# relay_pro_eagle7x.net
KiCad netlist of a schematic drawn in EAGLE
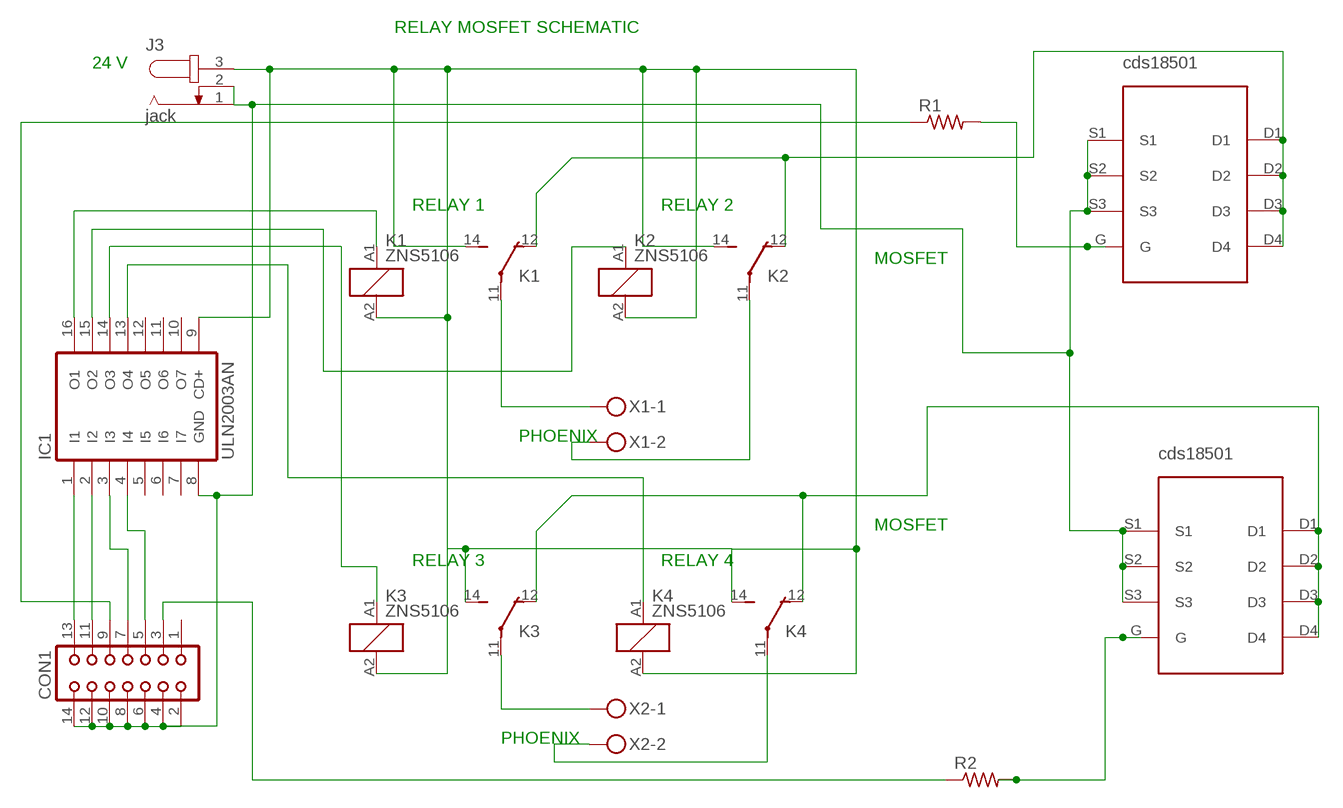
[diagram p0: schematic, sheet 1]

(export (version "E")
  (design (tool "Eeschema 10.0.6"))
  (components
    (comp (ref "CON1")
      (value "CON14")
      (footprint "eagle-import:CON14")
      (libsource (lib "eagle-import") (part "CON14"))
    )
    (comp (ref "IC1")
      (value "ULN2003AN")
      (footprint "eagle-import:DIL16")
      (libsource (lib "eagle-import") (part "ULN2003AN"))
    )
    (comp (ref "J3")
      (value "jack")
      (footprint "eagle-import:SPC4077")
      (libsource (lib "eagle-import") (part "JACK-PLUG0"))
    )
    (comp (ref "K1")
      (value "ZNS5106")
      (footprint "eagle-import:ZN5")
      (libsource (lib "eagle-import") (part "ZNS5106"))
    )
    (comp (ref "K2")
      (value "ZNS5106")
      (footprint "eagle-import:ZN5")
      (libsource (lib "eagle-import") (part "ZNS5106"))
    )
    (comp (ref "K3")
      (value "ZNS5106")
      (footprint "eagle-import:ZN5")
      (libsource (lib "eagle-import") (part "ZNS5106"))
    )
    (comp (ref "K4")
      (value "ZNS5106")
      (footprint "eagle-import:ZN5")
      (libsource (lib "eagle-import") (part "ZNS5106"))
    )
    (comp (ref "R1")
      (value "R-US_R0603")
      (footprint "eagle-import:R0603")
      (libsource (lib "eagle-import") (part "R-US_R0603"))
    )
    (comp (ref "R2")
      (value "R-US_R0603")
      (footprint "eagle-import:R0603")
      (libsource (lib "eagle-import") (part "R-US_R0603"))
    )
    (comp (ref "U$1")
      (value "CSD18503GDS-NEW")
      (footprint "eagle-import:CDS")
      (libsource (lib "eagle-import") (part "CSD18503GDS-NEW"))
    )
    (comp (ref "U$2")
      (value "CSD18503GDS-NEW")
      (footprint "eagle-import:CDS")
      (libsource (lib "eagle-import") (part "CSD18503GDS-NEW"))
    )
    (comp (ref "X1")
      (value "MKDSN1,5/2-5,08")
      (footprint "eagle-import:MKDSN1,5_2-5,08")
      (libsource (lib "eagle-import") (part "MKDSN1,5/2-5,08"))
    )
    (comp (ref "X2")
      (value "MKDSN1,5/2-5,08")
      (footprint "eagle-import:MKDSN1,5_2-5,08")
      (libsource (lib "eagle-import") (part "MKDSN1,5/2-5,08"))
    )
  )
  (nets
    (net (code "1") (name "Net-(CON1-Pad3)") (class "Default")
      (node (ref "CON1") (pin "3") (pinfunction "3_3") (pintype "passive"))
      (node (ref "R2") (pin "1") (pinfunction "1_1") (pintype "passive"))
    )
    (net (code "2") (name "Net-(CON1-Pad9)") (class "Default")
      (node (ref "CON1") (pin "9") (pinfunction "9_9") (pintype "passive"))
      (node (ref "R1") (pin "1") (pinfunction "1_1") (pintype "passive"))
    )
    (net (code "3") (name "Net-(IC1-CD+)") (class "Default")
      (node (ref "IC1") (pin "9") (pinfunction "CD+_9") (pintype "passive"))
      (node (ref "J3") (pin "3") (pinfunction "3_3") (pintype "passive"))
      (node (ref "K1") (pin "14") (pinfunction "S_14") (pintype "passive"))
      (node (ref "K1") (pin "A2") (pinfunction "2_A2") (pintype "passive"))
      (node (ref "K2") (pin "14") (pinfunction "S_14") (pintype "passive"))
      (node (ref "K2") (pin "A2") (pinfunction "2_A2") (pintype "passive"))
      (node (ref "K3") (pin "14") (pinfunction "S_14") (pintype "passive"))
      (node (ref "K3") (pin "A2") (pinfunction "2_A2") (pintype "passive"))
      (node (ref "K4") (pin "14") (pinfunction "S_14") (pintype "passive"))
      (node (ref "K4") (pin "A2") (pinfunction "2_A2") (pintype "passive"))
    )
    (net (code "4") (name "Net-(IC1-GND)") (class "Default")
      (node (ref "CON1") (pin "10") (pinfunction "10_10") (pintype "passive"))
      (node (ref "CON1") (pin "12") (pinfunction "12_12") (pintype "passive"))
      (node (ref "CON1") (pin "14") (pinfunction "14_14") (pintype "passive"))
      (node (ref "CON1") (pin "2") (pinfunction "2_2") (pintype "passive"))
      (node (ref "CON1") (pin "4") (pinfunction "4_4") (pintype "passive"))
      (node (ref "CON1") (pin "6") (pinfunction "6_6") (pintype "passive"))
      (node (ref "CON1") (pin "8") (pinfunction "8_8") (pintype "passive"))
      (node (ref "IC1") (pin "8") (pinfunction "GND_8") (pintype "power_in"))
      (node (ref "J3") (pin "1") (pinfunction "1_1") (pintype "passive"))
      (node (ref "J3") (pin "2") (pinfunction "2_2") (pintype "passive"))
      (node (ref "U$1") (pin "S1") (pinfunction "S1_S1") (pintype "bidirectional"))
      (node (ref "U$1") (pin "S2") (pinfunction "S2_S2") (pintype "bidirectional"))
      (node (ref "U$1") (pin "S3") (pinfunction "S3_S3") (pintype "bidirectional"))
      (node (ref "U$2") (pin "S1") (pinfunction "S1_S1") (pintype "bidirectional"))
      (node (ref "U$2") (pin "S2") (pinfunction "S2_S2") (pintype "bidirectional"))
      (node (ref "U$2") (pin "S3") (pinfunction "S3_S3") (pintype "bidirectional"))
    )
    (net (code "5") (name "Net-(IC1-I1)") (class "Default")
      (node (ref "CON1") (pin "13") (pinfunction "13_13") (pintype "passive"))
      (node (ref "IC1") (pin "1") (pinfunction "I1_1") (pintype "input"))
    )
    (net (code "6") (name "Net-(IC1-I2)") (class "Default")
      (node (ref "CON1") (pin "11") (pinfunction "11_11") (pintype "passive"))
      (node (ref "IC1") (pin "2") (pinfunction "I2_2") (pintype "input"))
    )
    (net (code "7") (name "Net-(IC1-I3)") (class "Default")
      (node (ref "CON1") (pin "7") (pinfunction "7_7") (pintype "passive"))
      (node (ref "IC1") (pin "3") (pinfunction "I3_3") (pintype "input"))
    )
    (net (code "8") (name "Net-(IC1-I4)") (class "Default")
      (node (ref "CON1") (pin "5") (pinfunction "5_5") (pintype "passive"))
      (node (ref "IC1") (pin "4") (pinfunction "I4_4") (pintype "input"))
    )
    (net (code "9") (name "Net-(IC1-O1)") (class "Default")
      (node (ref "IC1") (pin "16") (pinfunction "O1_16") (pintype "open_collector"))
      (node (ref "K1") (pin "A1") (pinfunction "1_A1") (pintype "passive"))
    )
    (net (code "10") (name "Net-(IC1-O2)") (class "Default")
      (node (ref "IC1") (pin "15") (pinfunction "O2_15") (pintype "open_collector"))
      (node (ref "K2") (pin "A1") (pinfunction "1_A1") (pintype "passive"))
    )
    (net (code "11") (name "Net-(IC1-O3)") (class "Default")
      (node (ref "IC1") (pin "14") (pinfunction "O3_14") (pintype "open_collector"))
      (node (ref "K3") (pin "A1") (pinfunction "1_A1") (pintype "passive"))
    )
    (net (code "12") (name "Net-(IC1-O4)") (class "Default")
      (node (ref "IC1") (pin "13") (pinfunction "O4_13") (pintype "open_collector"))
      (node (ref "K4") (pin "A1") (pinfunction "1_A1") (pintype "passive"))
    )
    (net (code "13") (name "Net-(K1B-O)") (class "Default")
      (node (ref "K1") (pin "12") (pinfunction "O_12") (pintype "passive"))
      (node (ref "K2") (pin "12") (pinfunction "O_12") (pintype "passive"))
      (node (ref "U$1") (pin "D1") (pinfunction "D1_D1") (pintype "bidirectional"))
      (node (ref "U$1") (pin "D2") (pinfunction "D2_D2") (pintype "bidirectional"))
      (node (ref "U$1") (pin "D3") (pinfunction "D3_D3") (pintype "bidirectional"))
      (node (ref "U$1") (pin "D4") (pinfunction "D4_D4") (pintype "bidirectional"))
    )
    (net (code "14") (name "Net-(K1B-P)") (class "Default")
      (node (ref "K1") (pin "11") (pinfunction "P_11") (pintype "passive"))
      (node (ref "X1") (pin "1") (pinfunction "KL_1") (pintype "passive"))
    )
    (net (code "15") (name "Net-(K2B-P)") (class "Default")
      (node (ref "K2") (pin "11") (pinfunction "P_11") (pintype "passive"))
      (node (ref "X1") (pin "2") (pinfunction "KL_2") (pintype "passive"))
    )
    (net (code "16") (name "Net-(K3B-O)") (class "Default")
      (node (ref "K3") (pin "12") (pinfunction "O_12") (pintype "passive"))
      (node (ref "K4") (pin "12") (pinfunction "O_12") (pintype "passive"))
      (node (ref "U$2") (pin "D1") (pinfunction "D1_D1") (pintype "bidirectional"))
      (node (ref "U$2") (pin "D2") (pinfunction "D2_D2") (pintype "bidirectional"))
      (node (ref "U$2") (pin "D3") (pinfunction "D3_D3") (pintype "bidirectional"))
      (node (ref "U$2") (pin "D4") (pinfunction "D4_D4") (pintype "bidirectional"))
    )
    (net (code "17") (name "Net-(K3B-P)") (class "Default")
      (node (ref "K3") (pin "11") (pinfunction "P_11") (pintype "passive"))
      (node (ref "X2") (pin "1") (pinfunction "KL_1") (pintype "passive"))
    )
    (net (code "18") (name "Net-(K4B-P)") (class "Default")
      (node (ref "K4") (pin "11") (pinfunction "P_11") (pintype "passive"))
      (node (ref "X2") (pin "2") (pinfunction "KL_2") (pintype "passive"))
    )
    (net (code "19") (name "Net-(R1-Pad2)") (class "Default")
      (node (ref "R1") (pin "2") (pinfunction "2_2") (pintype "passive"))
      (node (ref "U$1") (pin "G") (pinfunction "G_G") (pintype "bidirectional"))
    )
    (net (code "20") (name "Net-(R2-Pad2)") (class "Default")
      (node (ref "R2") (pin "2") (pinfunction "2_2") (pintype "passive"))
      (node (ref "U$2") (pin "G") (pinfunction "G_G") (pintype "bidirectional"))
    )
    (net (code "21") (name "unconnected-(CON1-Pad1)") (class "Default")
      (node (ref "CON1") (pin "1") (pinfunction "1_1") (pintype "passive"))
    )
    (net (code "22") (name "unconnected-(IC1-I5-Pad5)") (class "Default")
      (node (ref "IC1") (pin "5") (pinfunction "I5_5") (pintype "input"))
    )
    (net (code "23") (name "unconnected-(IC1-I6-Pad6)") (class "Default")
      (node (ref "IC1") (pin "6") (pinfunction "I6_6") (pintype "input"))
    )
    (net (code "24") (name "unconnected-(IC1-I7-Pad7)") (class "Default")
      (node (ref "IC1") (pin "7") (pinfunction "I7_7") (pintype "input"))
    )
    (net (code "25") (name "unconnected-(IC1-O5-Pad12)") (class "Default")
      (node (ref "IC1") (pin "12") (pinfunction "O5_12") (pintype "open_collector"))
    )
    (net (code "26") (name "unconnected-(IC1-O6-Pad11)") (class "Default")
      (node (ref "IC1") (pin "11") (pinfunction "O6_11") (pintype "open_collector"))
    )
    (net (code "27") (name "unconnected-(IC1-O7-Pad10)") (class "Default")
      (node (ref "IC1") (pin "10") (pinfunction "O7_10") (pintype "open_collector"))
    )
  )
)
